# gc_adapt.net
KiCad netlist of a schematic drawn in EAGLE
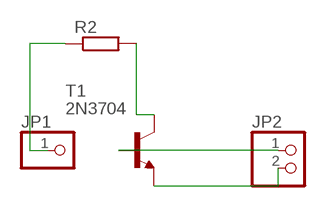
[diagram p0: schematic, sheet 1]

(export (version "E")
  (design (tool "Eeschema 10.0.6"))
  (components
    (comp (ref "JP1")
      (value "PINHD-1X1")
      (footprint "eagle-import:1X01")
      (libsource (lib "eagle-import") (part "PINHD-1X1"))
    )
    (comp (ref "JP2")
      (value "PINHD-1X2")
      (footprint "eagle-import:1X02")
      (libsource (lib "eagle-import") (part "PINHD-1X2"))
    )
    (comp (ref "R2")
      (value "R-EU_0204/5")
      (footprint "eagle-import:0204_5")
      (libsource (lib "eagle-import") (part "R-EU_0204/5"))
    )
    (comp (ref "T1")
      (value "2N3704")
      (footprint "eagle-import:TO92")
      (libsource (lib "eagle-import") (part "2N3704"))
    )
  )
  (nets
    (net (code "1") (name "Net-(JP1-Pad1)") (class "Default")
      (node (ref "JP1") (pin "1") (pinfunction "1_1") (pintype "passive"))
      (node (ref "R2") (pin "1") (pinfunction "1_1") (pintype "passive"))
    )
    (net (code "2") (name "Net-(T1-B)") (class "Default")
      (node (ref "JP2") (pin "1") (pinfunction "1_1") (pintype "passive"))
      (node (ref "T1") (pin "1") (pinfunction "B_1") (pintype "passive"))
    )
    (net (code "3") (name "Net-(T1-C)") (class "Default")
      (node (ref "R2") (pin "2") (pinfunction "2_2") (pintype "passive"))
      (node (ref "T1") (pin "2") (pinfunction "C_2") (pintype "passive"))
    )
    (net (code "4") (name "Net-(T1-E)") (class "Default")
      (node (ref "JP2") (pin "2") (pinfunction "2_2") (pintype "passive"))
      (node (ref "T1") (pin "3") (pinfunction "E_3") (pintype "passive"))
    )
  )
)
